# midi_pad_laser_optimized.net
KiCad netlist of a schematic drawn in EAGLE
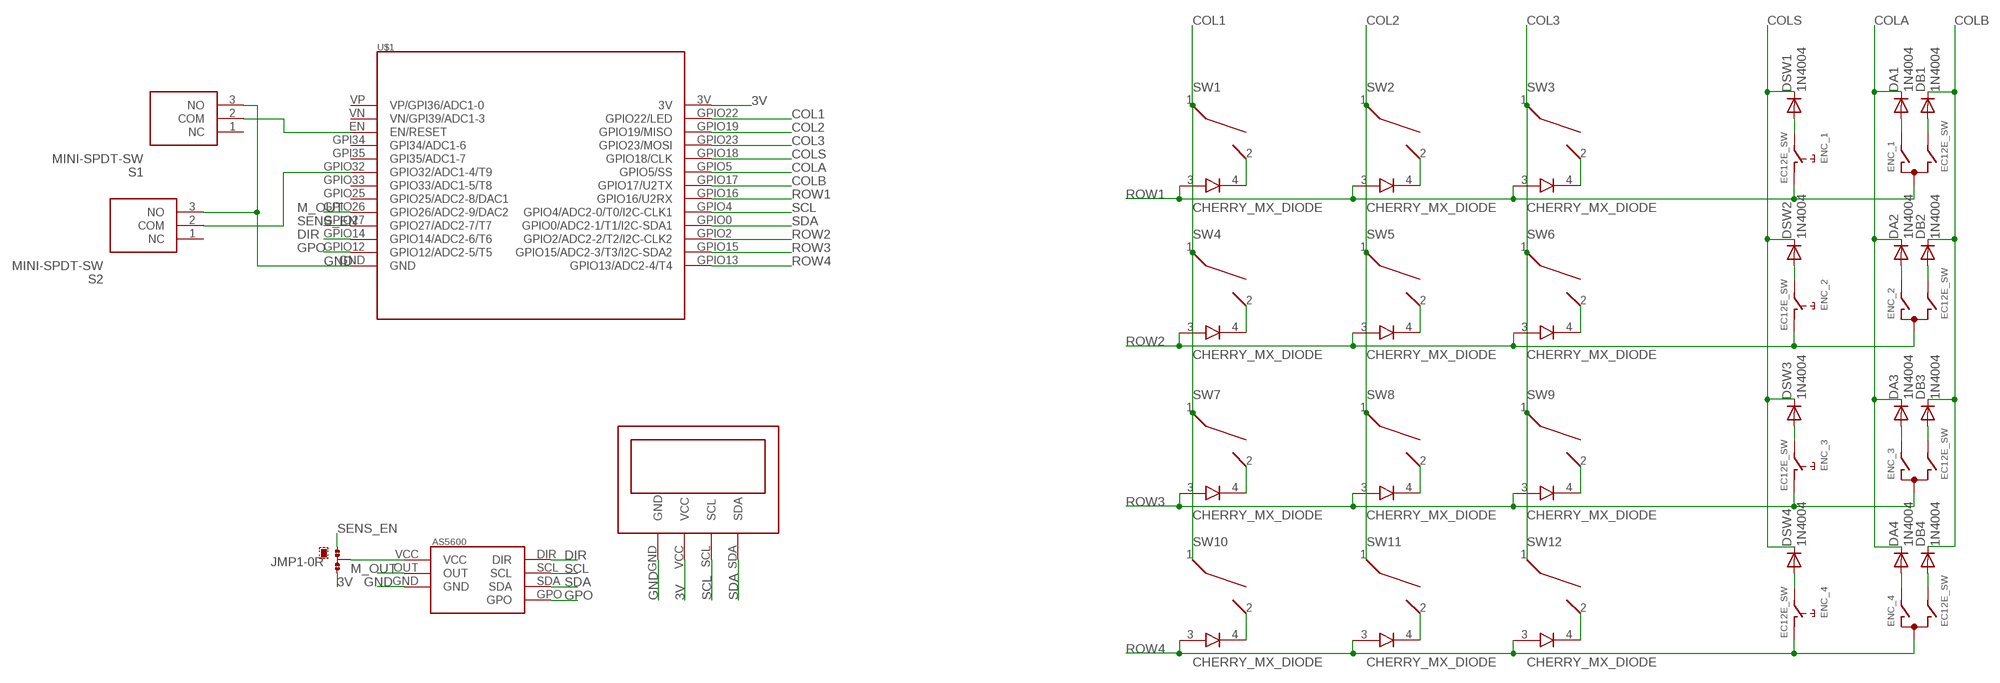
[diagram p0: schematic, sheet 1]

(export (version "E")
  (design (tool "Eeschema 10.0.6"))
  (components
    (comp (ref "DA1")
      (value "1N4004")
      (footprint "eagle-import:DO41-10")
      (libsource (lib "eagle-import") (part "1N4004"))
    )
    (comp (ref "DA2")
      (value "1N4004")
      (footprint "eagle-import:DO41-10")
      (libsource (lib "eagle-import") (part "1N4004"))
    )
    (comp (ref "DA3")
      (value "1N4004")
      (footprint "eagle-import:DO41-10")
      (libsource (lib "eagle-import") (part "1N4004"))
    )
    (comp (ref "DA4")
      (value "1N4004")
      (footprint "eagle-import:DO41-10")
      (libsource (lib "eagle-import") (part "1N4004"))
    )
    (comp (ref "DB1")
      (value "1N4004")
      (footprint "eagle-import:DO41-10")
      (libsource (lib "eagle-import") (part "1N4004"))
    )
    (comp (ref "DB2")
      (value "1N4004")
      (footprint "eagle-import:DO41-10")
      (libsource (lib "eagle-import") (part "1N4004"))
    )
    (comp (ref "DB3")
      (value "1N4004")
      (footprint "eagle-import:DO41-10")
      (libsource (lib "eagle-import") (part "1N4004"))
    )
    (comp (ref "DB4")
      (value "1N4004")
      (footprint "eagle-import:DO41-10")
      (libsource (lib "eagle-import") (part "1N4004"))
    )
    (comp (ref "DSW1")
      (value "1N4004")
      (footprint "eagle-import:DO41-10")
      (libsource (lib "eagle-import") (part "1N4004"))
    )
    (comp (ref "DSW2")
      (value "1N4004")
      (footprint "eagle-import:DO41-10")
      (libsource (lib "eagle-import") (part "1N4004"))
    )
    (comp (ref "DSW3")
      (value "1N4004")
      (footprint "eagle-import:DO41-10")
      (libsource (lib "eagle-import") (part "1N4004"))
    )
    (comp (ref "DSW4")
      (value "1N4004")
      (footprint "eagle-import:DO41-10")
      (libsource (lib "eagle-import") (part "1N4004"))
    )
    (comp (ref "ENC_1")
      (value "EC12E_SW")
      (footprint "eagle-import:ALPS_EC12E_SW")
      (fields (field (name "MPN") "EC12E2424407"))
      (libsource (lib "eagle-import") (part "EC12E_SW"))
    )
    (comp (ref "ENC_2")
      (value "EC12E_SW")
      (footprint "eagle-import:ALPS_EC12E_SW")
      (fields (field (name "MPN") "EC12E2424407"))
      (libsource (lib "eagle-import") (part "EC12E_SW"))
    )
    (comp (ref "ENC_3")
      (value "EC12E_SW")
      (footprint "eagle-import:ALPS_EC12E_SW")
      (fields (field (name "MPN") "EC12E2424407"))
      (libsource (lib "eagle-import") (part "EC12E_SW"))
    )
    (comp (ref "ENC_4")
      (value "EC12E_SW")
      (footprint "eagle-import:ALPS_EC12E_SW")
      (fields (field (name "MPN") "EC12E2424407"))
      (libsource (lib "eagle-import") (part "EC12E_SW"))
    )
    (comp (ref "JMP1")
      (value "0R-JUMPA")
      (footprint "eagle-import:A0R-JMP")
      (libsource (lib "eagle-import") (part "0R-JUMPA"))
    )
    (comp (ref "S1")
      (value "MINI-SPDT-SW")
      (footprint "eagle-import:MINISPDTSW")
      (fields (field (name "MOUSER_PART_NUMBER") "992-MINI-SPDT-SW"))
      (libsource (lib "eagle-import") (part "MINI-SPDT-SW"))
    )
    (comp (ref "S2")
      (value "MINI-SPDT-SW")
      (footprint "eagle-import:MINISPDTSW")
      (fields (field (name "MOUSER_PART_NUMBER") "992-MINI-SPDT-SW"))
      (libsource (lib "eagle-import") (part "MINI-SPDT-SW"))
    )
    (comp (ref "SW1")
      (value "CHERRY_MX_DIODE")
      (footprint "eagle-import:MX1A-XX[D_J]N")
      (libsource (lib "eagle-import") (part "CHERRY_MX_DIODE"))
    )
    (comp (ref "SW2")
      (value "CHERRY_MX_DIODE")
      (footprint "eagle-import:MX1A-XX[D_J]N")
      (libsource (lib "eagle-import") (part "CHERRY_MX_DIODE"))
    )
    (comp (ref "SW3")
      (value "CHERRY_MX_DIODE")
      (footprint "eagle-import:MX1A-XX[D_J]N")
      (libsource (lib "eagle-import") (part "CHERRY_MX_DIODE"))
    )
    (comp (ref "SW4")
      (value "CHERRY_MX_DIODE")
      (footprint "eagle-import:MX1A-XX[D_J]N")
      (libsource (lib "eagle-import") (part "CHERRY_MX_DIODE"))
    )
    (comp (ref "SW5")
      (value "CHERRY_MX_DIODE")
      (footprint "eagle-import:MX1A-XX[D_J]N")
      (libsource (lib "eagle-import") (part "CHERRY_MX_DIODE"))
    )
    (comp (ref "SW6")
      (value "CHERRY_MX_DIODE")
      (footprint "eagle-import:MX1A-XX[D_J]N")
      (libsource (lib "eagle-import") (part "CHERRY_MX_DIODE"))
    )
    (comp (ref "SW7")
      (value "CHERRY_MX_DIODE")
      (footprint "eagle-import:MX1A-XX[D_J]N")
      (libsource (lib "eagle-import") (part "CHERRY_MX_DIODE"))
    )
    (comp (ref "SW8")
      (value "CHERRY_MX_DIODE")
      (footprint "eagle-import:MX1A-XX[D_J]N")
      (libsource (lib "eagle-import") (part "CHERRY_MX_DIODE"))
    )
    (comp (ref "SW9")
      (value "CHERRY_MX_DIODE")
      (footprint "eagle-import:MX1A-XX[D_J]N")
      (libsource (lib "eagle-import") (part "CHERRY_MX_DIODE"))
    )
    (comp (ref "SW10")
      (value "CHERRY_MX_DIODE")
      (footprint "eagle-import:MX1A-XX[D_J]N")
      (libsource (lib "eagle-import") (part "CHERRY_MX_DIODE"))
    )
    (comp (ref "SW11")
      (value "CHERRY_MX_DIODE")
      (footprint "eagle-import:MX1A-XX[D_J]N")
      (libsource (lib "eagle-import") (part "CHERRY_MX_DIODE"))
    )
    (comp (ref "SW12")
      (value "CHERRY_MX_DIODE")
      (footprint "eagle-import:MX1A-XX[D_J]N")
      (libsource (lib "eagle-import") (part "CHERRY_MX_DIODE"))
    )
    (comp (ref "U$1")
      (value "LOLIN32_LITE")
      (footprint "eagle-import:LOLIN32_LITE")
      (libsource (lib "eagle-import") (part "LOLIN32_LITE"))
    )
    (comp (ref "U$2")
      (value "AS5600_BREAKOUT")
      (footprint "eagle-import:AS5600_BREAKOUT")
      (libsource (lib "eagle-import") (part "AS5600_BREAKOUT"))
    )
    (comp (ref "U$3")
      (value "I2C_OLED_128X64")
      (footprint "eagle-import:I2C_OLED_128X64_BREAKOUT")
      (libsource (lib "eagle-import") (part "I2C_OLED_128X64"))
    )
  )
  (nets
    (net (code "1") (name "/3V") (class "Default")
      (node (ref "JMP1") (pin "3") (pinfunction "3_3") (pintype "passive"))
      (node (ref "U$1") (pin "3V") (pinfunction "3V_3V") (pintype "bidirectional"))
      (node (ref "U$3") (pin "VCC") (pinfunction "VCC_VCC") (pintype "bidirectional"))
    )
    (net (code "2") (name "/COL1") (class "Default")
      (node (ref "SW1") (pin "1") (pinfunction "1_1") (pintype "passive"))
      (node (ref "SW10") (pin "1") (pinfunction "1_1") (pintype "passive"))
      (node (ref "SW4") (pin "1") (pinfunction "1_1") (pintype "passive"))
      (node (ref "SW7") (pin "1") (pinfunction "1_1") (pintype "passive"))
      (node (ref "U$1") (pin "GPIO22") (pinfunction "GPIO22/LED_GPIO22") (pintype "bidirectional"))
    )
    (net (code "3") (name "/COL2") (class "Default")
      (node (ref "SW11") (pin "1") (pinfunction "1_1") (pintype "passive"))
      (node (ref "SW2") (pin "1") (pinfunction "1_1") (pintype "passive"))
      (node (ref "SW5") (pin "1") (pinfunction "1_1") (pintype "passive"))
      (node (ref "SW8") (pin "1") (pinfunction "1_1") (pintype "passive"))
      (node (ref "U$1") (pin "GPIO19") (pinfunction "GPIO19/MISO_GPIO19") (pintype "bidirectional"))
    )
    (net (code "4") (name "/COL3") (class "Default")
      (node (ref "SW12") (pin "1") (pinfunction "1_1") (pintype "passive"))
      (node (ref "SW3") (pin "1") (pinfunction "1_1") (pintype "passive"))
      (node (ref "SW6") (pin "1") (pinfunction "1_1") (pintype "passive"))
      (node (ref "SW9") (pin "1") (pinfunction "1_1") (pintype "passive"))
      (node (ref "U$1") (pin "GPIO23") (pinfunction "GPIO23/MOSI_GPIO23") (pintype "bidirectional"))
    )
    (net (code "5") (name "/COLA") (class "Default")
      (node (ref "DA1") (pin "C") (pinfunction "C_C") (pintype "passive"))
      (node (ref "DA2") (pin "C") (pinfunction "C_C") (pintype "passive"))
      (node (ref "DA3") (pin "C") (pinfunction "C_C") (pintype "passive"))
      (node (ref "DA4") (pin "C") (pinfunction "C_C") (pintype "passive"))
      (node (ref "U$1") (pin "GPIO5") (pinfunction "GPIO5/SS_GPIO5") (pintype "bidirectional"))
    )
    (net (code "6") (name "/COLB") (class "Default")
      (node (ref "DB1") (pin "C") (pinfunction "C_C") (pintype "passive"))
      (node (ref "DB2") (pin "C") (pinfunction "C_C") (pintype "passive"))
      (node (ref "DB3") (pin "C") (pinfunction "C_C") (pintype "passive"))
      (node (ref "DB4") (pin "C") (pinfunction "C_C") (pintype "passive"))
      (node (ref "U$1") (pin "GPIO17") (pinfunction "GPIO17/U2TX_GPIO17") (pintype "bidirectional"))
    )
    (net (code "7") (name "/COLS") (class "Default")
      (node (ref "DSW1") (pin "C") (pinfunction "C_C") (pintype "passive"))
      (node (ref "DSW2") (pin "C") (pinfunction "C_C") (pintype "passive"))
      (node (ref "DSW3") (pin "C") (pinfunction "C_C") (pintype "passive"))
      (node (ref "DSW4") (pin "C") (pinfunction "C_C") (pintype "passive"))
      (node (ref "U$1") (pin "GPIO18") (pinfunction "GPIO18/CLK_GPIO18") (pintype "bidirectional"))
    )
    (net (code "8") (name "/DIR") (class "Default")
      (node (ref "U$1") (pin "GPIO14") (pinfunction "GPIO14/ADC2-6/T6_GPIO14") (pintype "bidirectional"))
      (node (ref "U$2") (pin "DIR") (pinfunction "DIR_DIR") (pintype "bidirectional"))
    )
    (net (code "9") (name "/GND") (class "Default")
      (node (ref "S1") (pin "3") (pinfunction "NO_3") (pintype "bidirectional"))
      (node (ref "S2") (pin "3") (pinfunction "NO_3") (pintype "bidirectional"))
      (node (ref "U$1") (pin "GND") (pinfunction "GND_GND") (pintype "bidirectional"))
      (node (ref "U$2") (pin "GND") (pinfunction "GND_GND") (pintype "bidirectional"))
      (node (ref "U$3") (pin "GND") (pinfunction "GND_GND") (pintype "bidirectional"))
    )
    (net (code "10") (name "/GPO") (class "Default")
      (node (ref "U$1") (pin "GPIO12") (pinfunction "GPIO12/ADC2-5/T5_GPIO12") (pintype "bidirectional"))
      (node (ref "U$2") (pin "GPO") (pinfunction "GPO_GPO") (pintype "bidirectional"))
    )
    (net (code "11") (name "/M_OUT") (class "Default")
      (node (ref "U$1") (pin "GPIO26") (pinfunction "GPIO26/ADC2-9/DAC2_GPIO26") (pintype "bidirectional"))
      (node (ref "U$2") (pin "OUT") (pinfunction "OUT_OUT") (pintype "bidirectional"))
    )
    (net (code "12") (name "/ROW1") (class "Default")
      (node (ref "ENC_1") (pin "C") (pinfunction "C_C") (pintype "passive"))
      (node (ref "ENC_1") (pin "D") (pinfunction "1_D") (pintype "passive"))
      (node (ref "SW1") (pin "3") (pinfunction "3_3") (pintype "passive"))
      (node (ref "SW2") (pin "3") (pinfunction "3_3") (pintype "passive"))
      (node (ref "SW3") (pin "3") (pinfunction "3_3") (pintype "passive"))
      (node (ref "U$1") (pin "GPIO16") (pinfunction "GPIO16/U2RX_GPIO16") (pintype "bidirectional"))
    )
    (net (code "13") (name "/ROW2") (class "Default")
      (node (ref "ENC_2") (pin "C") (pinfunction "C_C") (pintype "passive"))
      (node (ref "ENC_2") (pin "D") (pinfunction "1_D") (pintype "passive"))
      (node (ref "SW4") (pin "3") (pinfunction "3_3") (pintype "passive"))
      (node (ref "SW5") (pin "3") (pinfunction "3_3") (pintype "passive"))
      (node (ref "SW6") (pin "3") (pinfunction "3_3") (pintype "passive"))
      (node (ref "U$1") (pin "GPIO2") (pinfunction "GPIO2/ADC2-2/T2/I2C-CLK2_GPIO2") (pintype "bidirectional"))
    )
    (net (code "14") (name "/ROW3") (class "Default")
      (node (ref "ENC_3") (pin "C") (pinfunction "C_C") (pintype "passive"))
      (node (ref "ENC_3") (pin "D") (pinfunction "1_D") (pintype "passive"))
      (node (ref "SW7") (pin "3") (pinfunction "3_3") (pintype "passive"))
      (node (ref "SW8") (pin "3") (pinfunction "3_3") (pintype "passive"))
      (node (ref "SW9") (pin "3") (pinfunction "3_3") (pintype "passive"))
      (node (ref "U$1") (pin "GPIO15") (pinfunction "GPIO15/ADC2-3/T3/I2C-SDA2_GPIO15") (pintype "bidirectional"))
    )
    (net (code "15") (name "/ROW4") (class "Default")
      (node (ref "ENC_4") (pin "C") (pinfunction "C_C") (pintype "passive"))
      (node (ref "ENC_4") (pin "D") (pinfunction "1_D") (pintype "passive"))
      (node (ref "SW10") (pin "3") (pinfunction "3_3") (pintype "passive"))
      (node (ref "SW11") (pin "3") (pinfunction "3_3") (pintype "passive"))
      (node (ref "SW12") (pin "3") (pinfunction "3_3") (pintype "passive"))
      (node (ref "U$1") (pin "GPIO13") (pinfunction "GPIO13/ADC2-4/T4_GPIO13") (pintype "bidirectional"))
    )
    (net (code "16") (name "/SCL") (class "Default")
      (node (ref "U$1") (pin "GPIO4") (pinfunction "GPIO4/ADC2-0/T0/I2C-CLK1_GPIO4") (pintype "bidirectional"))
      (node (ref "U$2") (pin "SCL") (pinfunction "SCL_SCL") (pintype "bidirectional"))
      (node (ref "U$3") (pin "SCL") (pinfunction "SCL_SCL") (pintype "bidirectional"))
    )
    (net (code "17") (name "/SDA") (class "Default")
      (node (ref "U$1") (pin "GPIO0") (pinfunction "GPIO0/ADC2-1/T1/I2C-SDA1_GPIO0") (pintype "bidirectional"))
      (node (ref "U$2") (pin "SDA") (pinfunction "SDA_SDA") (pintype "bidirectional"))
      (node (ref "U$3") (pin "SDA") (pinfunction "SDA_SDA") (pintype "bidirectional"))
    )
    (net (code "18") (name "/SENS_EN") (class "Default")
      (node (ref "JMP1") (pin "1") (pinfunction "1_1") (pintype "passive"))
      (node (ref "U$1") (pin "GPIO27") (pinfunction "GPIO27/ADC2-7/T7_GPIO27") (pintype "bidirectional"))
    )
    (net (code "19") (name "Net-(DA1-PadA)") (class "Default")
      (node (ref "DA1") (pin "A") (pinfunction "A_A") (pintype "passive"))
      (node (ref "ENC_1") (pin "A") (pinfunction "A_A") (pintype "passive"))
    )
    (net (code "20") (name "Net-(DA2-PadA)") (class "Default")
      (node (ref "DA2") (pin "A") (pinfunction "A_A") (pintype "passive"))
      (node (ref "ENC_2") (pin "A") (pinfunction "A_A") (pintype "passive"))
    )
    (net (code "21") (name "Net-(DA3-PadA)") (class "Default")
      (node (ref "DA3") (pin "A") (pinfunction "A_A") (pintype "passive"))
      (node (ref "ENC_3") (pin "A") (pinfunction "A_A") (pintype "passive"))
    )
    (net (code "22") (name "Net-(DA4-PadA)") (class "Default")
      (node (ref "DA4") (pin "A") (pinfunction "A_A") (pintype "passive"))
      (node (ref "ENC_4") (pin "A") (pinfunction "A_A") (pintype "passive"))
    )
    (net (code "23") (name "Net-(DB1-PadA)") (class "Default")
      (node (ref "DB1") (pin "A") (pinfunction "A_A") (pintype "passive"))
      (node (ref "ENC_1") (pin "B") (pinfunction "B_B") (pintype "passive"))
    )
    (net (code "24") (name "Net-(DB2-PadA)") (class "Default")
      (node (ref "DB2") (pin "A") (pinfunction "A_A") (pintype "passive"))
      (node (ref "ENC_2") (pin "B") (pinfunction "B_B") (pintype "passive"))
    )
    (net (code "25") (name "Net-(DB3-PadA)") (class "Default")
      (node (ref "DB3") (pin "A") (pinfunction "A_A") (pintype "passive"))
      (node (ref "ENC_3") (pin "B") (pinfunction "B_B") (pintype "passive"))
    )
    (net (code "26") (name "Net-(DB4-PadA)") (class "Default")
      (node (ref "DB4") (pin "A") (pinfunction "A_A") (pintype "passive"))
      (node (ref "ENC_4") (pin "B") (pinfunction "B_B") (pintype "passive"))
    )
    (net (code "27") (name "Net-(ENC_1B-2)") (class "Default")
      (node (ref "DSW1") (pin "A") (pinfunction "A_A") (pintype "passive"))
      (node (ref "ENC_1") (pin "E") (pinfunction "2_E") (pintype "passive"))
    )
    (net (code "28") (name "Net-(ENC_2B-2)") (class "Default")
      (node (ref "DSW2") (pin "A") (pinfunction "A_A") (pintype "passive"))
      (node (ref "ENC_2") (pin "E") (pinfunction "2_E") (pintype "passive"))
    )
    (net (code "29") (name "Net-(ENC_3B-2)") (class "Default")
      (node (ref "DSW3") (pin "A") (pinfunction "A_A") (pintype "passive"))
      (node (ref "ENC_3") (pin "E") (pinfunction "2_E") (pintype "passive"))
    )
    (net (code "30") (name "Net-(ENC_4B-2)") (class "Default")
      (node (ref "DSW4") (pin "A") (pinfunction "A_A") (pintype "passive"))
      (node (ref "ENC_4") (pin "E") (pinfunction "2_E") (pintype "passive"))
    )
    (net (code "31") (name "Net-(JMP1-Pad2)") (class "Default")
      (node (ref "JMP1") (pin "2") (pinfunction "2_2") (pintype "passive"))
      (node (ref "U$2") (pin "VCC") (pinfunction "VCC_VCC") (pintype "bidirectional"))
    )
    (net (code "32") (name "Net-(S1-COM)") (class "Default")
      (node (ref "S1") (pin "2") (pinfunction "COM_2") (pintype "bidirectional"))
      (node (ref "U$1") (pin "EN") (pinfunction "EN/RESET_EN") (pintype "bidirectional"))
    )
    (net (code "33") (name "Net-(S2-COM)") (class "Default")
      (node (ref "S2") (pin "2") (pinfunction "COM_2") (pintype "bidirectional"))
      (node (ref "U$1") (pin "GPIO32") (pinfunction "GPIO32/ADC1-4/T9_GPIO32") (pintype "bidirectional"))
    )
    (net (code "34") (name "Net-(SW1-Pad2)") (class "Default")
      (node (ref "SW1") (pin "2") (pinfunction "2_2") (pintype "passive"))
      (node (ref "SW1") (pin "4") (pinfunction "4_4") (pintype "passive"))
    )
    (net (code "35") (name "Net-(SW2-Pad2)") (class "Default")
      (node (ref "SW2") (pin "2") (pinfunction "2_2") (pintype "passive"))
      (node (ref "SW2") (pin "4") (pinfunction "4_4") (pintype "passive"))
    )
    (net (code "36") (name "Net-(SW3-Pad2)") (class "Default")
      (node (ref "SW3") (pin "2") (pinfunction "2_2") (pintype "passive"))
      (node (ref "SW3") (pin "4") (pinfunction "4_4") (pintype "passive"))
    )
    (net (code "37") (name "Net-(SW4-Pad2)") (class "Default")
      (node (ref "SW4") (pin "2") (pinfunction "2_2") (pintype "passive"))
      (node (ref "SW4") (pin "4") (pinfunction "4_4") (pintype "passive"))
    )
    (net (code "38") (name "Net-(SW5-Pad2)") (class "Default")
      (node (ref "SW5") (pin "2") (pinfunction "2_2") (pintype "passive"))
      (node (ref "SW5") (pin "4") (pinfunction "4_4") (pintype "passive"))
    )
    (net (code "39") (name "Net-(SW6-Pad2)") (class "Default")
      (node (ref "SW6") (pin "2") (pinfunction "2_2") (pintype "passive"))
      (node (ref "SW6") (pin "4") (pinfunction "4_4") (pintype "passive"))
    )
    (net (code "40") (name "Net-(SW7-Pad2)") (class "Default")
      (node (ref "SW7") (pin "2") (pinfunction "2_2") (pintype "passive"))
      (node (ref "SW7") (pin "4") (pinfunction "4_4") (pintype "passive"))
    )
    (net (code "41") (name "Net-(SW8-Pad2)") (class "Default")
      (node (ref "SW8") (pin "2") (pinfunction "2_2") (pintype "passive"))
      (node (ref "SW8") (pin "4") (pinfunction "4_4") (pintype "passive"))
    )
    (net (code "42") (name "Net-(SW9-Pad2)") (class "Default")
      (node (ref "SW9") (pin "2") (pinfunction "2_2") (pintype "passive"))
      (node (ref "SW9") (pin "4") (pinfunction "4_4") (pintype "passive"))
    )
    (net (code "43") (name "Net-(SW10-Pad2)") (class "Default")
      (node (ref "SW10") (pin "2") (pinfunction "2_2") (pintype "passive"))
      (node (ref "SW10") (pin "4") (pinfunction "4_4") (pintype "passive"))
    )
    (net (code "44") (name "Net-(SW11-Pad2)") (class "Default")
      (node (ref "SW11") (pin "2") (pinfunction "2_2") (pintype "passive"))
      (node (ref "SW11") (pin "4") (pinfunction "4_4") (pintype "passive"))
    )
    (net (code "45") (name "Net-(SW12-Pad2)") (class "Default")
      (node (ref "SW12") (pin "2") (pinfunction "2_2") (pintype "passive"))
      (node (ref "SW12") (pin "4") (pinfunction "4_4") (pintype "passive"))
    )
    (net (code "46") (name "unconnected-(S1-NC-Pad1)") (class "Default")
      (node (ref "S1") (pin "1") (pinfunction "NC_1") (pintype "no_connect"))
    )
    (net (code "47") (name "unconnected-(S2-NC-Pad1)") (class "Default")
      (node (ref "S2") (pin "1") (pinfunction "NC_1") (pintype "no_connect"))
    )
    (net (code "48") (name "unconnected-(U$1-GPI34{slash}ADC1-6-PadGPI34)") (class "Default")
      (node (ref "U$1") (pin "GPI34") (pinfunction "GPI34/ADC1-6_GPI34") (pintype "bidirectional"))
    )
    (net (code "49") (name "unconnected-(U$1-GPI35{slash}ADC1-7-PadGPI35)") (class "Default")
      (node (ref "U$1") (pin "GPI35") (pinfunction "GPI35/ADC1-7_GPI35") (pintype "bidirectional"))
    )
    (net (code "50") (name "unconnected-(U$1-GPIO25{slash}ADC2-8{slash}DAC1-PadGPIO25)") (class "Default")
      (node (ref "U$1") (pin "GPIO25") (pinfunction "GPIO25/ADC2-8/DAC1_GPIO25") (pintype "bidirectional"))
    )
    (net (code "51") (name "unconnected-(U$1-GPIO33{slash}ADC1-5{slash}T8-PadGPIO33)") (class "Default")
      (node (ref "U$1") (pin "GPIO33") (pinfunction "GPIO33/ADC1-5/T8_GPIO33") (pintype "bidirectional"))
    )
    (net (code "52") (name "unconnected-(U$1-VN{slash}GPI39{slash}ADC1-3-PadVN)") (class "Default")
      (node (ref "U$1") (pin "VN") (pinfunction "VN/GPI39/ADC1-3_VN") (pintype "bidirectional"))
    )
    (net (code "53") (name "unconnected-(U$1-VP{slash}GPI36{slash}ADC1-0-PadVP)") (class "Default")
      (node (ref "U$1") (pin "VP") (pinfunction "VP/GPI36/ADC1-0_VP") (pintype "bidirectional"))
    )
  )
)
